# Sheet1.net
KiCad netlist of a schematic drawn in Altium Designer
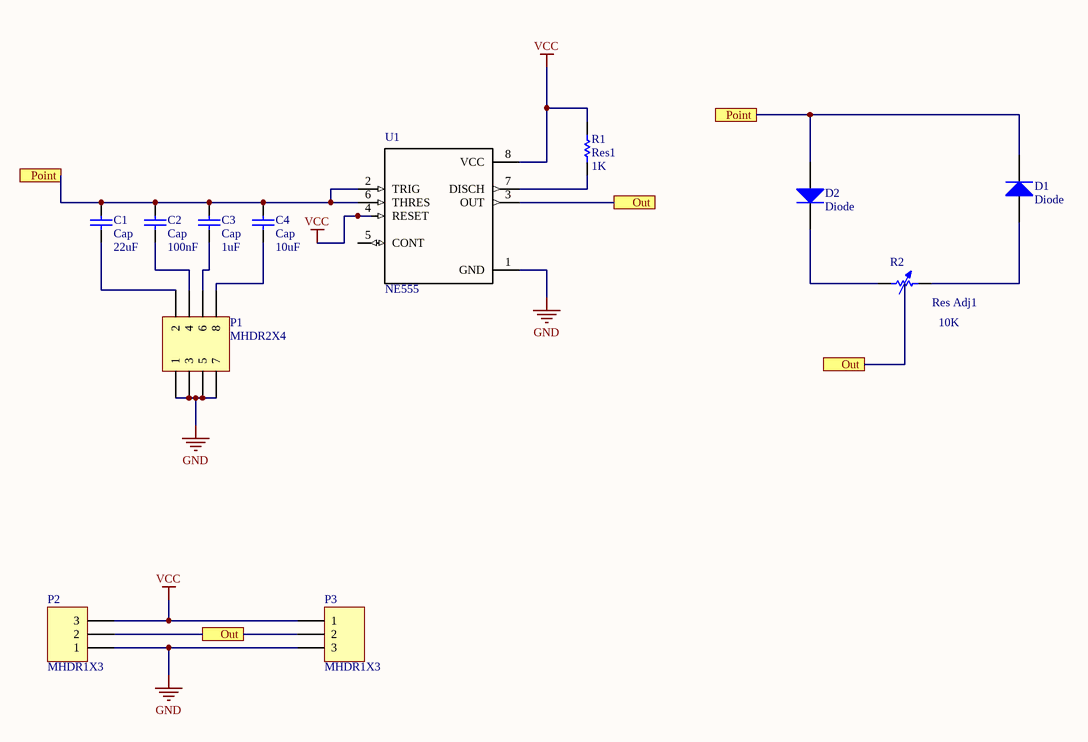
[diagram p0: Sheet1.SchDoc]

(export (version "E")
  (design (tool "Eeschema 10.0.6"))
  (components
    (comp (ref "C1")
      (value "Cap")
      (footprint "RAD-0.3")
      (description "Capacitor")
      (fields (field (name "ALTIUM_VALUE") "22uF") (field (name "PUBLISHER") "Altium Limited"))
      (libsource (lib "Miscellaneous Devices") (part "Cap"))
    )
    (comp (ref "C2")
      (value "Cap")
      (footprint "RAD-0.3")
      (description "Capacitor")
      (fields (field (name "ALTIUM_VALUE") "100nF") (field (name "PUBLISHER") "Altium Limited"))
      (libsource (lib "Miscellaneous Devices") (part "Cap"))
    )
    (comp (ref "C3")
      (value "Cap")
      (footprint "RAD-0.3")
      (description "Capacitor")
      (fields (field (name "ALTIUM_VALUE") "1uF") (field (name "PUBLISHER") "Altium Limited"))
      (libsource (lib "Miscellaneous Devices") (part "Cap"))
    )
    (comp (ref "C4")
      (value "Cap")
      (footprint "RAD-0.3")
      (description "Capacitor")
      (fields (field (name "ALTIUM_VALUE") "10uF") (field (name "PUBLISHER") "Altium Limited"))
      (libsource (lib "Miscellaneous Devices") (part "Cap"))
    )
    (comp (ref "D1")
      (value "Diode")
      (footprint "DIODE-0.4")
      (description "Default Diode")
      (fields (field (name "PUBLISHER") "Altium Limited"))
      (libsource (lib "Miscellaneous Devices") (part "Diode"))
    )
    (comp (ref "D2")
      (value "Diode")
      (footprint "DIODE-0.4")
      (description "Default Diode")
      (fields (field (name "PUBLISHER") "Altium Limited"))
      (libsource (lib "Miscellaneous Devices") (part "Diode"))
    )
    (comp (ref "P1")
      (value "MHDR2X4")
      (footprint "HEADER_2X4")
      (description "Header, 4-Pin, Dual row")
      (fields (field (name "PUBLISHER") "Altium Limited"))
      (libsource (lib "Miscellaneous Connectors") (part "MHDR2X4"))
    )
    (comp (ref "P2")
      (value "MHDR1X3")
      (footprint "HEADER_1X3")
      (description "Header, 3-Pin")
      (fields (field (name "PUBLISHER") "Altium Limited"))
      (libsource (lib "") (part "MHDR1X3_1"))
    )
    (comp (ref "P3")
      (value "MHDR1X3")
      (footprint "CN_KRE_3")
      (description "Header, 3-Pin")
      (fields (field (name "PUBLISHER") "Altium Limited"))
      (libsource (lib "Miscellaneous Connectors") (part "MHDR1X3"))
    )
    (comp (ref "R1")
      (value "Res1")
      (footprint "AXIAL-0.3")
      (description "Resistor")
      (fields (field (name "ALTIUM_VALUE") "1K") (field (name "PUBLISHER") "Altium Limited"))
      (libsource (lib "Miscellaneous Devices") (part "Res1"))
    )
    (comp (ref "R2")
      (value "Res Adj1")
      (footprint "CN_KRE_3")
      (description "Variable Resistor")
      (fields (field (name "ALTIUM_VALUE") "10K") (field (name "PUBLISHER") "Altium Limited"))
      (libsource (lib "Miscellaneous Devices") (part "Res Adj1"))
    )
    (comp (ref "U1")
      (value "NE555")
      (footprint "*DIP794W45P254L1060H508Q8")
      (fields (field (name "MF") "Texas Instruments") (field (name "DIGI-KEY_PART_NUMBER") "296-6501-1-ND"))
      (libsource (lib "NE555") (part "NE555"))
    )
  )
  (nets
    (net (code "1") (name "/Out") (class "Default")
      (node (ref "P2") (pin "2") (pinfunction "2_2") (pintype "passive"))
      (node (ref "P3") (pin "2") (pinfunction "2_2") (pintype "passive"))
      (node (ref "U1") (pin "3") (pinfunction "OUT_3") (pintype "output"))
    )
    (net (code "2") (name "/Point") (class "Default")
      (node (ref "C1") (pin "2") (pinfunction "2_2") (pintype "passive"))
      (node (ref "C2") (pin "2") (pinfunction "2_2") (pintype "passive"))
      (node (ref "C3") (pin "2") (pinfunction "2_2") (pintype "passive"))
      (node (ref "C4") (pin "2") (pinfunction "2_2") (pintype "passive"))
      (node (ref "D1") (pin "2") (pinfunction "K_2") (pintype "passive"))
      (node (ref "D2") (pin "1") (pinfunction "A_1") (pintype "passive"))
      (node (ref "U1") (pin "2") (pinfunction "TRIG_2") (pintype "input"))
      (node (ref "U1") (pin "6") (pinfunction "THRES_6") (pintype "input"))
    )
    (net (code "3") (name "GND") (class "Default")
      (node (ref "P1") (pin "1") (pinfunction "1_1") (pintype "passive"))
      (node (ref "P1") (pin "3") (pinfunction "3_3") (pintype "passive"))
      (node (ref "P1") (pin "5") (pinfunction "5_5") (pintype "passive"))
      (node (ref "P1") (pin "7") (pinfunction "7_7") (pintype "passive"))
      (node (ref "P2") (pin "1") (pinfunction "1_1") (pintype "passive"))
      (node (ref "P3") (pin "3") (pinfunction "3_3") (pintype "passive"))
      (node (ref "U1") (pin "1") (pinfunction "GND_1") (pintype "power_in"))
    )
    (net (code "4") (name "Net-(C1-Pad1)") (class "Default")
      (node (ref "C1") (pin "1") (pinfunction "1_1") (pintype "passive"))
      (node (ref "P1") (pin "2") (pinfunction "2_2") (pintype "passive"))
    )
    (net (code "5") (name "Net-(C2-Pad1)") (class "Default")
      (node (ref "C2") (pin "1") (pinfunction "1_1") (pintype "passive"))
      (node (ref "P1") (pin "4") (pinfunction "4_4") (pintype "passive"))
    )
    (net (code "6") (name "Net-(C3-Pad1)") (class "Default")
      (node (ref "C3") (pin "1") (pinfunction "1_1") (pintype "passive"))
      (node (ref "P1") (pin "6") (pinfunction "6_6") (pintype "passive"))
    )
    (net (code "7") (name "Net-(C4-Pad1)") (class "Default")
      (node (ref "C4") (pin "1") (pinfunction "1_1") (pintype "passive"))
      (node (ref "P1") (pin "8") (pinfunction "8_8") (pintype "passive"))
    )
    (net (code "8") (name "Net-(D1-A)") (class "Default")
      (node (ref "D1") (pin "1") (pinfunction "A_1") (pintype "passive"))
      (node (ref "R2") (pin "2") (pinfunction "2_2") (pintype "passive"))
    )
    (net (code "9") (name "Net-(D2-K)") (class "Default")
      (node (ref "D2") (pin "2") (pinfunction "K_2") (pintype "passive"))
      (node (ref "R2") (pin "1") (pinfunction "1_1") (pintype "passive"))
    )
    (net (code "10") (name "Net-(U1-DISCH)") (class "Default")
      (node (ref "R1") (pin "1") (pinfunction "1_1") (pintype "passive"))
      (node (ref "U1") (pin "7") (pinfunction "DISCH_7") (pintype "output"))
    )
    (net (code "11") (name "VCC") (class "Default")
      (node (ref "P2") (pin "3") (pinfunction "3_3") (pintype "passive"))
      (node (ref "P3") (pin "1") (pinfunction "1_1") (pintype "passive"))
      (node (ref "R1") (pin "2") (pinfunction "2_2") (pintype "passive"))
      (node (ref "U1") (pin "4") (pinfunction "RESET_4") (pintype "input"))
      (node (ref "U1") (pin "8") (pinfunction "VCC_8") (pintype "power_in"))
    )
    (net (code "12") (name "unconnected-(U1-CONT-Pad5)") (class "Default")
      (node (ref "U1") (pin "5") (pinfunction "CONT_5") (pintype "bidirectional"))
    )
  )
)
